# transfo_schematic.net
KiCad netlist of a schematic drawn in EAGLE
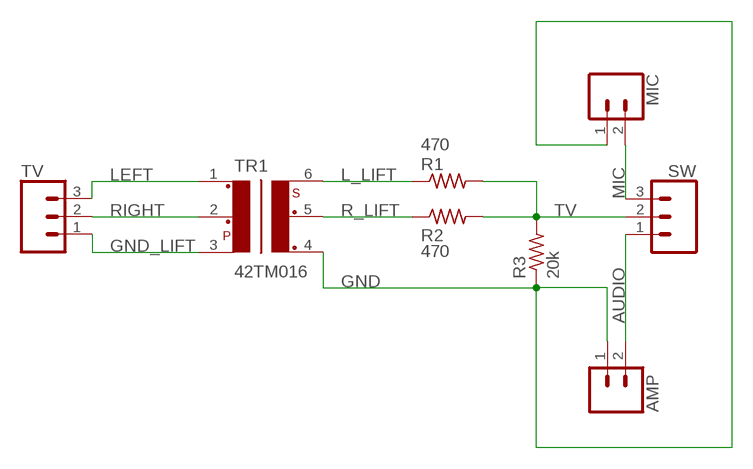
[diagram p0: schematic, sheet 1]

(export (version "E")
  (design (tool "Eeschema 10.0.6"))
  (components
    (comp (ref "AMP")
      (value "CONN_02POLAR")
      (footprint "eagle-import:MOLEX-1X2")
      (libsource (lib "eagle-import") (part "CONN_02POLAR"))
    )
    (comp (ref "MIC")
      (value "CONN_02POLAR")
      (footprint "eagle-import:MOLEX-1X2")
      (libsource (lib "eagle-import") (part "CONN_02POLAR"))
    )
    (comp (ref "R1")
      (value "470")
      (footprint "eagle-import:0204_7")
      (libsource (lib "eagle-import") (part "R-US_0204/7"))
    )
    (comp (ref "R2")
      (value "470")
      (footprint "eagle-import:0204_7")
      (libsource (lib "eagle-import") (part "R-US_0204/7"))
    )
    (comp (ref "R3")
      (value "20k")
      (footprint "eagle-import:0204_7")
      (libsource (lib "eagle-import") (part "R-US_0204/7"))
    )
    (comp (ref "SW")
      (value "CONN_03POLAR")
      (footprint "eagle-import:MOLEX-1X3")
      (libsource (lib "eagle-import") (part "CONN_03POLAR"))
    )
    (comp (ref "TR1")
      (value "42TM016")
      (footprint "eagle-import:42TM")
      (libsource (lib "eagle-import") (part "42T?M016"))
    )
    (comp (ref "TV")
      (value "CONN_03POLAR")
      (footprint "eagle-import:MOLEX-1X3")
      (libsource (lib "eagle-import") (part "CONN_03POLAR"))
    )
  )
  (nets
    (net (code "1") (name "/AUDIO") (class "Default")
      (node (ref "AMP") (pin "2") (pinfunction "2_2") (pintype "passive"))
      (node (ref "SW") (pin "1") (pinfunction "1_1") (pintype "passive"))
    )
    (net (code "2") (name "/GND") (class "Default")
      (node (ref "AMP") (pin "1") (pinfunction "1_1") (pintype "passive"))
      (node (ref "MIC") (pin "1") (pinfunction "1_1") (pintype "passive"))
      (node (ref "R3") (pin "1") (pinfunction "1_1") (pintype "passive"))
      (node (ref "TR1") (pin "4") (pinfunction "4_4") (pintype "passive"))
    )
    (net (code "3") (name "/GND_LIFT") (class "Default")
      (node (ref "TR1") (pin "3") (pinfunction "3_3") (pintype "passive"))
      (node (ref "TV") (pin "1") (pinfunction "1_1") (pintype "passive"))
    )
    (net (code "4") (name "/LEFT") (class "Default")
      (node (ref "TR1") (pin "1") (pinfunction "1_1") (pintype "passive"))
      (node (ref "TV") (pin "3") (pinfunction "3_3") (pintype "passive"))
    )
    (net (code "5") (name "/L_LIFT") (class "Default")
      (node (ref "R1") (pin "1") (pinfunction "1_1") (pintype "passive"))
      (node (ref "TR1") (pin "6") (pinfunction "6_6") (pintype "passive"))
    )
    (net (code "6") (name "/MIC") (class "Default")
      (node (ref "MIC") (pin "2") (pinfunction "2_2") (pintype "passive"))
      (node (ref "SW") (pin "3") (pinfunction "3_3") (pintype "passive"))
    )
    (net (code "7") (name "/RIGHT") (class "Default")
      (node (ref "TR1") (pin "2") (pinfunction "2_2") (pintype "passive"))
      (node (ref "TV") (pin "2") (pinfunction "2_2") (pintype "passive"))
    )
    (net (code "8") (name "/R_LIFT") (class "Default")
      (node (ref "R2") (pin "1") (pinfunction "1_1") (pintype "passive"))
      (node (ref "TR1") (pin "5") (pinfunction "5_5") (pintype "passive"))
    )
    (net (code "9") (name "/TV") (class "Default")
      (node (ref "R1") (pin "2") (pinfunction "2_2") (pintype "passive"))
      (node (ref "R2") (pin "2") (pinfunction "2_2") (pintype "passive"))
      (node (ref "R3") (pin "2") (pinfunction "2_2") (pintype "passive"))
      (node (ref "SW") (pin "2") (pinfunction "2_2") (pintype "passive"))
    )
  )
)
